# PuertosSensores.net
KiCad netlist of a schematic drawn in Altium Designer
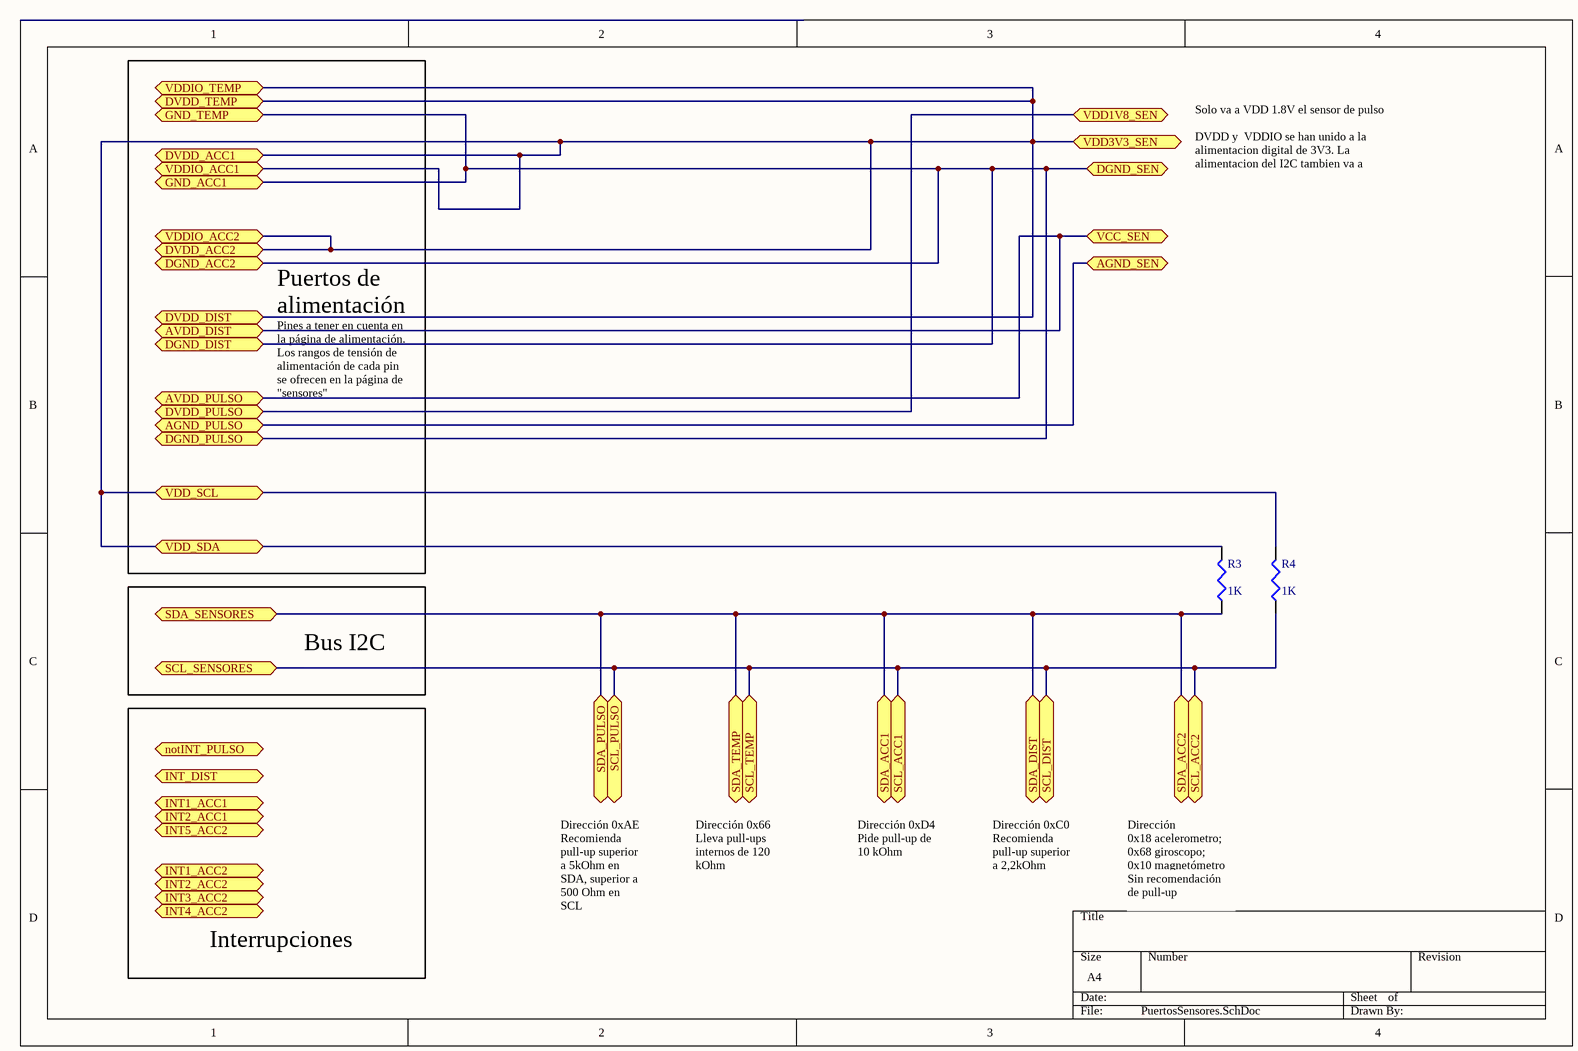
[diagram p0: PuertosSensores.SchDoc]

(export (version "E")
  (design (tool "Eeschema 10.0.6"))
  (components
    (comp (ref "R3")
      (value "1K")
      (footprint "J1-0603")
      (description "Resistor")
      (fields (field (name "PUBLISHER") "Altium Limited"))
      (libsource (lib "Miscellaneous Devices") (part "Res3"))
    )
    (comp (ref "R4")
      (value "1K")
      (footprint "J1-0603")
      (description "Resistor")
      (fields (field (name "PUBLISHER") "Altium Limited"))
      (libsource (lib "Miscellaneous Devices") (part "Res3"))
    )
  )
  (nets
    (net (code "4") (name "/DVDD_ACC1") (class "Default")
      (node (ref "R3") (pin "2") (pinfunction "2_2") (pintype "passive"))
      (node (ref "R4") (pin "2") (pinfunction "2_2") (pintype "passive"))
    )
    (net (code "14") (name "/SCL_ACC1") (class "Default")
      (node (ref "R4") (pin "1") (pinfunction "1_1") (pintype "passive"))
    )
    (net (code "15") (name "/SDA_ACC1") (class "Default")
      (node (ref "R3") (pin "1") (pinfunction "1_1") (pintype "passive"))
    )
  )
)
